# furby_shield_v1b.net
KiCad netlist of a schematic drawn in EAGLE
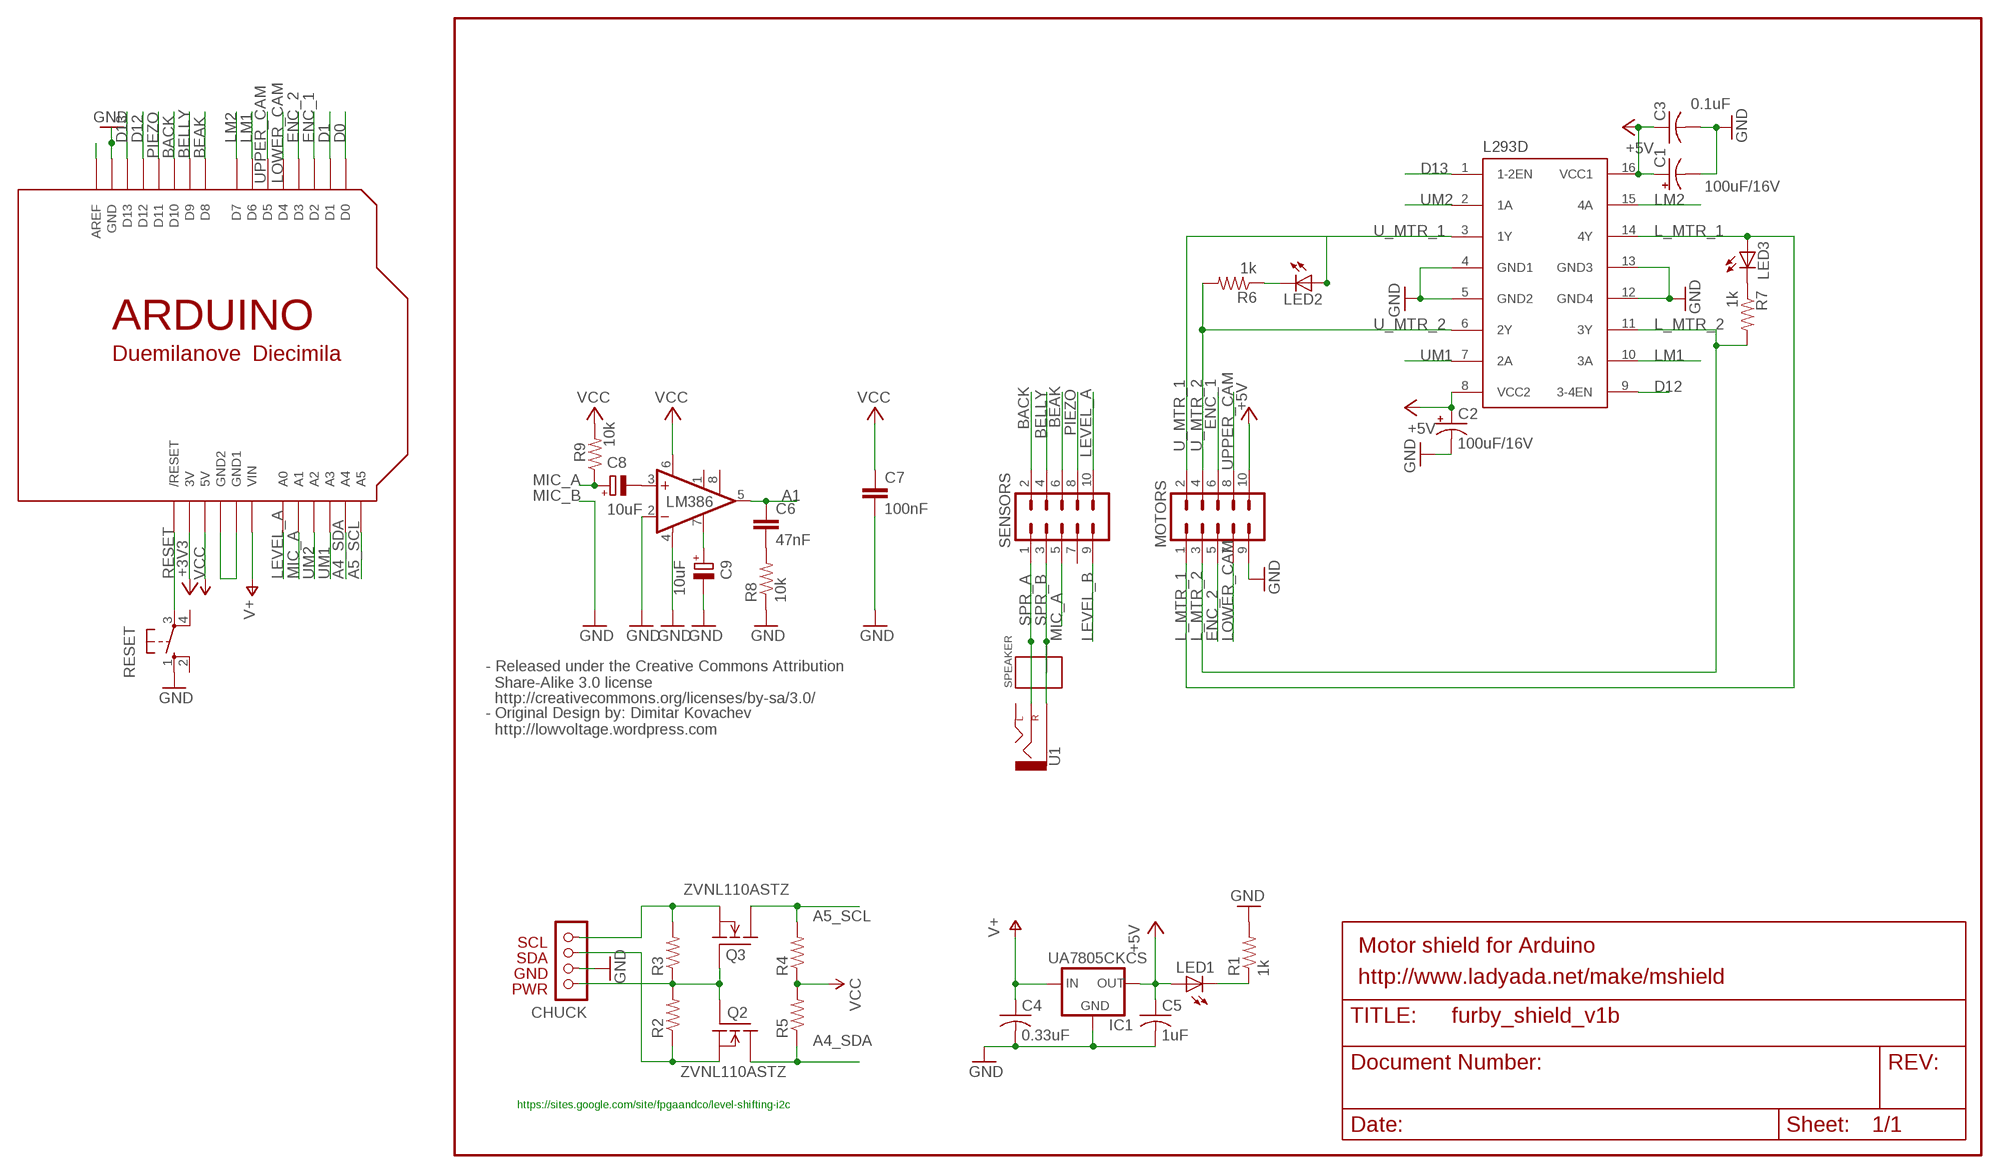
[diagram p0: schematic, sheet 1]

(export (version "E")
  (design (tool "Eeschema 10.0.6"))
  (components
    (comp (ref "C1")
      (value "100uF/16V")
      (footprint "eagle-import:E2,5-6")
      (libsource (lib "eagle-import") (part "CPOL-USE2.5-6"))
    )
    (comp (ref "C2")
      (value "100uF/16V")
      (footprint "eagle-import:E2,5-6")
      (libsource (lib "eagle-import") (part "CPOL-USE2.5-6"))
    )
    (comp (ref "C3")
      (value "0.1uF")
      (footprint "eagle-import:C025-025X050")
      (libsource (lib "eagle-import") (part "rcl-ez_C-US025-025X050"))
    )
    (comp (ref "C4")
      (value "0.33uF")
      (footprint "eagle-import:C025-024X044")
      (libsource (lib "eagle-import") (part "C-US025-024X044"))
    )
    (comp (ref "C5")
      (value "1uF")
      (footprint "eagle-import:C025-024X044")
      (libsource (lib "eagle-import") (part "C-US025-024X044"))
    )
    (comp (ref "C6")
      (value "47nF")
      (footprint "eagle-import:C025-030X050")
      (libsource (lib "eagle-import") (part "C-EU025-030X050"))
    )
    (comp (ref "C7")
      (value "100nF")
      (footprint "eagle-import:C025-025X050")
      (libsource (lib "eagle-import") (part "C-EU025-025X050"))
    )
    (comp (ref "C8")
      (value "10uF")
      (footprint "eagle-import:E2,5-6")
      (libsource (lib "eagle-import") (part "CPOL-EUE2.5-6"))
    )
    (comp (ref "C9")
      (value "10uF")
      (footprint "eagle-import:E2,5-6")
      (libsource (lib "eagle-import") (part "CPOL-EUE2.5-6"))
    )
    (comp (ref "CHUCK")
      (value "NUNCHUCK")
      (footprint "eagle-import:CONN")
      (libsource (lib "eagle-import") (part "NUNCHUCK"))
    )
    (comp (ref "IC1")
      (value "UA7805CKCS")
      (footprint "eagle-import:TO-220-ALT")
      (libsource (lib "eagle-import") (part "V_REG_78XX-TO-220"))
    )
    (comp (ref "L293D")
      (value "L293E")
      (footprint "eagle-import:DIL16")
      (libsource (lib "eagle-import") (part "L293E"))
    )
    (comp (ref "LED1")
      (value "LED3MM")
      (footprint "eagle-import:LED3MM")
      (libsource (lib "eagle-import") (part "LED3MM"))
    )
    (comp (ref "LED2")
      (value "LED3MM")
      (footprint "eagle-import:LED3MM")
      (libsource (lib "eagle-import") (part "LED3MM"))
    )
    (comp (ref "LED3")
      (value "LED3MM")
      (footprint "eagle-import:LED3MM")
      (libsource (lib "eagle-import") (part "LED3MM"))
    )
    (comp (ref "LM386")
      (value "LM386N-1")
      (footprint "eagle-import:DIL08")
      (libsource (lib "eagle-import") (part "LM386?-N1"))
    )
    (comp (ref "MOTORS")
      (value "M05X2SHD")
      (footprint "eagle-import:2X5-SHROUDED")
      (libsource (lib "eagle-import") (part "M05X2SHD"))
    )
    (comp (ref "Q2")
      (value "ZVNL110ASTZ")
      (footprint "eagle-import:TO92-INLINE")
      (libsource (lib "eagle-import") (part "FQN1N50CI"))
    )
    (comp (ref "Q3")
      (value "ZVNL110ASTZ")
      (footprint "eagle-import:TO92-INLINE")
      (libsource (lib "eagle-import") (part "FQN1N50CI"))
    )
    (comp (ref "R1")
      (value "1k")
      (footprint "eagle-import:0204_5")
      (libsource (lib "eagle-import") (part "R-US_0204/5"))
    )
    (comp (ref "R2")
      (value "R-US_0204/7")
      (footprint "eagle-import:0204_7")
      (libsource (lib "eagle-import") (part "R-US_0204/7"))
    )
    (comp (ref "R3")
      (value "R-US_0204/7")
      (footprint "eagle-import:0204_7")
      (libsource (lib "eagle-import") (part "R-US_0204/7"))
    )
    (comp (ref "R4")
      (value "R-US_0204/7")
      (footprint "eagle-import:0204_7")
      (libsource (lib "eagle-import") (part "R-US_0204/7"))
    )
    (comp (ref "R5")
      (value "R-US_0204/7")
      (footprint "eagle-import:0204_7")
      (libsource (lib "eagle-import") (part "R-US_0204/7"))
    )
    (comp (ref "R6")
      (value "1k")
      (footprint "eagle-import:0204_5")
      (libsource (lib "eagle-import") (part "R-US_0204/5"))
    )
    (comp (ref "R7")
      (value "1k")
      (footprint "eagle-import:0204_5")
      (libsource (lib "eagle-import") (part "R-US_0204/5"))
    )
    (comp (ref "R8")
      (value "10k")
      (footprint "eagle-import:0204_7")
      (libsource (lib "eagle-import") (part "R-US_0204/7"))
    )
    (comp (ref "R9")
      (value "10k")
      (footprint "eagle-import:0204_7")
      (libsource (lib "eagle-import") (part "R-US_0204/7"))
    )
    (comp (ref "RESET")
      (value "10-XX")
      (footprint "eagle-import:B3F-10XX")
      (libsource (lib "eagle-import") (part "10-XX"))
    )
    (comp (ref "SENSORS")
      (value "M05X2SHD")
      (footprint "eagle-import:2X5-SHROUDED")
      (libsource (lib "eagle-import") (part "M05X2SHD"))
    )
    (comp (ref "SPEAKER")
      (value "TERMINAL2")
      (footprint "eagle-import:TERMINAL_2")
      (libsource (lib "eagle-import") (part "TERMINAL2"))
    )
    (comp (ref "U$1")
      (value "ARDUINO-NOHOLE")
      (footprint "eagle-import:ARDUINO-NOHOLE")
      (libsource (lib "eagle-import") (part "ARDUINO-NOHOLE"))
    )
    (comp (ref "U1")
      (value "AUDIO-JACKPTH")
      (footprint "eagle-import:AUDIO-JACK")
      (libsource (lib "eagle-import") (part "AUDIO-JACKPTH"))
    )
  )
  (nets
    (net (code "1") (name "+3V3") (class "Default")
      (node (ref "CHUCK") (pin "PWR") (pinfunction "PWR_PWR") (pintype "power_in"))
      (node (ref "Q2") (pin "2") (pinfunction "G_2") (pintype "passive"))
      (node (ref "Q3") (pin "2") (pinfunction "G_2") (pintype "passive"))
      (node (ref "R2") (pin "2") (pinfunction "2_2") (pintype "passive"))
      (node (ref "R3") (pin "1") (pinfunction "1_1") (pintype "passive"))
      (node (ref "U$1") (pin "3V") (pinfunction "3V_3V") (pintype "power_in"))
    )
    (net (code "2") (name "+5V") (class "Default")
      (node (ref "C1") (pin "+") (pinfunction "+_+") (pintype "passive"))
      (node (ref "C2") (pin "+") (pinfunction "+_+") (pintype "passive"))
      (node (ref "C3") (pin "1") (pinfunction "1_1") (pintype "passive"))
      (node (ref "C5") (pin "1") (pinfunction "1_1") (pintype "passive"))
      (node (ref "IC1") (pin "OUT") (pinfunction "OUT_OUT") (pintype "output"))
      (node (ref "L293D") (pin "16") (pinfunction "VCC1_16") (pintype "power_in"))
      (node (ref "L293D") (pin "8") (pinfunction "VCC2_8") (pintype "power_in"))
      (node (ref "LED1") (pin "A") (pinfunction "A_A") (pintype "passive"))
      (node (ref "MOTORS") (pin "10") (pinfunction "10_10") (pintype "passive"))
    )
    (net (code "3") (name "/A1") (class "Default")
      (node (ref "C6") (pin "1") (pinfunction "1_1") (pintype "passive"))
      (node (ref "LM386") (pin "5") (pinfunction "OUT_5") (pintype "output"))
    )
    (net (code "4") (name "/A4_SDA") (class "Default")
      (node (ref "Q2") (pin "1") (pinfunction "D_1") (pintype "passive"))
      (node (ref "R5") (pin "1") (pinfunction "1_1") (pintype "passive"))
      (node (ref "U$1") (pin "A4") (pinfunction "A4_A4") (pintype "bidirectional"))
    )
    (net (code "5") (name "/A5_SCL") (class "Default")
      (node (ref "Q3") (pin "1") (pinfunction "D_1") (pintype "passive"))
      (node (ref "R4") (pin "2") (pinfunction "2_2") (pintype "passive"))
      (node (ref "U$1") (pin "A5") (pinfunction "A5_A5") (pintype "bidirectional"))
    )
    (net (code "6") (name "/BACK") (class "Default")
      (node (ref "SENSORS") (pin "2") (pinfunction "2_2") (pintype "passive"))
      (node (ref "U$1") (pin "D10") (pinfunction "D10_D10") (pintype "bidirectional"))
    )
    (net (code "7") (name "/BEAK") (class "Default")
      (node (ref "SENSORS") (pin "6") (pinfunction "6_6") (pintype "passive"))
      (node (ref "U$1") (pin "D8") (pinfunction "D8_D8") (pintype "bidirectional"))
    )
    (net (code "8") (name "/BELLY") (class "Default")
      (node (ref "SENSORS") (pin "4") (pinfunction "4_4") (pintype "passive"))
      (node (ref "U$1") (pin "D9") (pinfunction "D9_D9") (pintype "bidirectional"))
    )
    (net (code "9") (name "/D0") (class "Default")
      (node (ref "U$1") (pin "D0") (pinfunction "D0_D0") (pintype "bidirectional"))
    )
    (net (code "10") (name "/D1") (class "Default")
      (node (ref "U$1") (pin "D1") (pinfunction "D1_D1") (pintype "bidirectional"))
    )
    (net (code "11") (name "/D12") (class "Default")
      (node (ref "L293D") (pin "9") (pinfunction "3-4EN_9") (pintype "input"))
      (node (ref "U$1") (pin "D12") (pinfunction "D12_D12") (pintype "bidirectional"))
    )
    (net (code "12") (name "/D13") (class "Default")
      (node (ref "L293D") (pin "1") (pinfunction "1-2EN_1") (pintype "input"))
      (node (ref "U$1") (pin "D13") (pinfunction "D13_D13") (pintype "bidirectional"))
    )
    (net (code "13") (name "/ENC_1") (class "Default")
      (node (ref "MOTORS") (pin "6") (pinfunction "6_6") (pintype "passive"))
      (node (ref "U$1") (pin "D2") (pinfunction "D2_D2") (pintype "bidirectional"))
    )
    (net (code "14") (name "/ENC_2") (class "Default")
      (node (ref "MOTORS") (pin "5") (pinfunction "5_5") (pintype "passive"))
      (node (ref "U$1") (pin "D3") (pinfunction "D3_D3") (pintype "bidirectional"))
    )
    (net (code "15") (name "/LEVEL_A") (class "Default")
      (node (ref "SENSORS") (pin "10") (pinfunction "10_10") (pintype "passive"))
      (node (ref "U$1") (pin "A0") (pinfunction "A0_A0") (pintype "bidirectional"))
    )
    (net (code "16") (name "/LEVEL_B") (class "Default")
      (node (ref "SENSORS") (pin "9") (pinfunction "9_9") (pintype "passive"))
    )
    (net (code "17") (name "/LM1") (class "Default")
      (node (ref "L293D") (pin "10") (pinfunction "3A_10") (pintype "input"))
      (node (ref "U$1") (pin "D6") (pinfunction "D6_D6") (pintype "bidirectional"))
    )
    (net (code "18") (name "/LM2") (class "Default")
      (node (ref "L293D") (pin "15") (pinfunction "4A_15") (pintype "input"))
      (node (ref "U$1") (pin "D7") (pinfunction "D7_D7") (pintype "bidirectional"))
    )
    (net (code "19") (name "/LOWER_CAM") (class "Default")
      (node (ref "MOTORS") (pin "7") (pinfunction "7_7") (pintype "passive"))
      (node (ref "U$1") (pin "D4") (pinfunction "D4_D4") (pintype "bidirectional"))
    )
    (net (code "20") (name "/L_MTR_1") (class "Default")
      (node (ref "L293D") (pin "14") (pinfunction "4Y_14") (pintype "output"))
      (node (ref "LED3") (pin "A") (pinfunction "A_A") (pintype "passive"))
      (node (ref "MOTORS") (pin "1") (pinfunction "1_1") (pintype "passive"))
    )
    (net (code "21") (name "/L_MTR_2") (class "Default")
      (node (ref "L293D") (pin "11") (pinfunction "3Y_11") (pintype "output"))
      (node (ref "MOTORS") (pin "3") (pinfunction "3_3") (pintype "passive"))
      (node (ref "R7") (pin "2") (pinfunction "2_2") (pintype "passive"))
    )
    (net (code "22") (name "/MIC_A") (class "Default")
      (node (ref "C8") (pin "+") (pinfunction "+_+") (pintype "passive"))
      (node (ref "R9") (pin "1") (pinfunction "1_1") (pintype "passive"))
      (node (ref "SENSORS") (pin "5") (pinfunction "5_5") (pintype "passive"))
      (node (ref "U$1") (pin "A1") (pinfunction "A1_A1") (pintype "bidirectional"))
    )
    (net (code "23") (name "/PIEZO") (class "Default")
      (node (ref "SENSORS") (pin "8") (pinfunction "8_8") (pintype "passive"))
      (node (ref "U$1") (pin "D11") (pinfunction "D11_D11") (pintype "bidirectional"))
    )
    (net (code "24") (name "/RESET") (class "Default")
      (node (ref "RESET") (pin "3") (pinfunction "P_3") (pintype "passive"))
      (node (ref "U$1") (pin "RESET") (pinfunction "/RESET_RESET") (pintype "bidirectional"))
    )
    (net (code "25") (name "/SPR_A") (class "Default")
      (node (ref "SENSORS") (pin "1") (pinfunction "1_1") (pintype "passive"))
      (node (ref "SPEAKER") (pin "P$1") (pinfunction "P$1_P$1") (pintype "bidirectional"))
      (node (ref "U1") (pin "RING") (pinfunction "RIGHT_RING") (pintype "bidirectional"))
    )
    (net (code "26") (name "/SPR_B") (class "Default")
      (node (ref "SENSORS") (pin "3") (pinfunction "3_3") (pintype "passive"))
      (node (ref "SPEAKER") (pin "P$2") (pinfunction "P$2_P$2") (pintype "bidirectional"))
      (node (ref "U1") (pin "SLEEVE") (pinfunction "SLEEVE_SLEEVE") (pintype "bidirectional"))
    )
    (net (code "27") (name "/UM1") (class "Default")
      (node (ref "L293D") (pin "7") (pinfunction "2A_7") (pintype "input"))
      (node (ref "U$1") (pin "A3") (pinfunction "A3_A3") (pintype "bidirectional"))
    )
    (net (code "28") (name "/UM2") (class "Default")
      (node (ref "L293D") (pin "2") (pinfunction "1A_2") (pintype "input"))
      (node (ref "U$1") (pin "A2") (pinfunction "A2_A2") (pintype "bidirectional"))
    )
    (net (code "29") (name "/UPPER_CAM") (class "Default")
      (node (ref "MOTORS") (pin "8") (pinfunction "8_8") (pintype "passive"))
      (node (ref "U$1") (pin "D5") (pinfunction "D5_D5") (pintype "bidirectional"))
    )
    (net (code "30") (name "/U_MTR_1") (class "Default")
      (node (ref "L293D") (pin "3") (pinfunction "1Y_3") (pintype "output"))
      (node (ref "LED2") (pin "A") (pinfunction "A_A") (pintype "passive"))
      (node (ref "MOTORS") (pin "2") (pinfunction "2_2") (pintype "passive"))
    )
    (net (code "31") (name "/U_MTR_2") (class "Default")
      (node (ref "L293D") (pin "6") (pinfunction "2Y_6") (pintype "output"))
      (node (ref "MOTORS") (pin "4") (pinfunction "4_4") (pintype "passive"))
      (node (ref "R6") (pin "2") (pinfunction "2_2") (pintype "passive"))
    )
    (net (code "32") (name "GND") (class "Default")
      (node (ref "C1") (pin "-") (pinfunction "-_-") (pintype "passive"))
      (node (ref "C2") (pin "-") (pinfunction "-_-") (pintype "passive"))
      (node (ref "C3") (pin "2") (pinfunction "2_2") (pintype "passive"))
      (node (ref "C4") (pin "2") (pinfunction "2_2") (pintype "passive"))
      (node (ref "C5") (pin "2") (pinfunction "2_2") (pintype "passive"))
      (node (ref "C7") (pin "2") (pinfunction "2_2") (pintype "passive"))
      (node (ref "C9") (pin "-") (pinfunction "-_-") (pintype "passive"))
      (node (ref "CHUCK") (pin "GND") (pinfunction "GND_GND") (pintype "passive"))
      (node (ref "IC1") (pin "GND") (pinfunction "GND_GND") (pintype "input"))
      (node (ref "L293D") (pin "12") (pinfunction "GND4_12") (pintype "power_in"))
      (node (ref "L293D") (pin "13") (pinfunction "GND3_13") (pintype "power_in"))
      (node (ref "L293D") (pin "4") (pinfunction "GND1_4") (pintype "power_in"))
      (node (ref "L293D") (pin "5") (pinfunction "GND2_5") (pintype "power_in"))
      (node (ref "LM386") (pin "2") (pinfunction "-IN_2") (pintype "input"))
      (node (ref "LM386") (pin "4") (pinfunction "GND_4") (pintype "power_in"))
      (node (ref "MOTORS") (pin "9") (pinfunction "9_9") (pintype "passive"))
      (node (ref "R1") (pin "2") (pinfunction "2_2") (pintype "passive"))
      (node (ref "R8") (pin "1") (pinfunction "1_1") (pintype "passive"))
      (node (ref "RESET") (pin "1") (pinfunction "S_1") (pintype "passive"))
      (node (ref "U$1") (pin "GND") (pinfunction "GND_GND") (pintype "power_in"))
      (node (ref "U$1") (pin "GND1") (pinfunction "GND1_GND1") (pintype "power_in"))
      (node (ref "U$1") (pin "GND2") (pinfunction "GND2_GND2") (pintype "power_in"))
    )
    (net (code "33") (name "Net-(C6-Pad2)") (class "Default")
      (node (ref "C6") (pin "2") (pinfunction "2_2") (pintype "passive"))
      (node (ref "R8") (pin "2") (pinfunction "2_2") (pintype "passive"))
    )
    (net (code "34") (name "Net-(LED1-C)") (class "Default")
      (node (ref "LED1") (pin "K") (pinfunction "C_K") (pintype "passive"))
      (node (ref "R1") (pin "1") (pinfunction "1_1") (pintype "passive"))
    )
    (net (code "35") (name "Net-(LED2-C)") (class "Default")
      (node (ref "LED2") (pin "K") (pinfunction "C_K") (pintype "passive"))
      (node (ref "R6") (pin "1") (pinfunction "1_1") (pintype "passive"))
    )
    (net (code "36") (name "Net-(LED3-C)") (class "Default")
      (node (ref "LED3") (pin "K") (pinfunction "C_K") (pintype "passive"))
      (node (ref "R7") (pin "1") (pinfunction "1_1") (pintype "passive"))
    )
    (net (code "37") (name "Net-(LM386-+IN)") (class "Default")
      (node (ref "C8") (pin "-") (pinfunction "-_-") (pintype "passive"))
      (node (ref "LM386") (pin "3") (pinfunction "+IN_3") (pintype "input"))
    )
    (net (code "38") (name "Net-(LM386-BYPASS)") (class "Default")
      (node (ref "C9") (pin "+") (pinfunction "+_+") (pintype "passive"))
      (node (ref "LM386") (pin "7") (pinfunction "BYPASS_7") (pintype "passive"))
    )
    (net (code "39") (name "Net-(Q2-S)") (class "Default")
      (node (ref "CHUCK") (pin "SDA") (pinfunction "SDA_SDA") (pintype "bidirectional"))
      (node (ref "Q2") (pin "3") (pinfunction "S_3") (pintype "passive"))
      (node (ref "R2") (pin "1") (pinfunction "1_1") (pintype "passive"))
    )
    (net (code "40") (name "Net-(Q3-S)") (class "Default")
      (node (ref "CHUCK") (pin "SCL") (pinfunction "SCL_SCL") (pintype "bidirectional"))
      (node (ref "Q3") (pin "3") (pinfunction "S_3") (pintype "passive"))
      (node (ref "R3") (pin "2") (pinfunction "2_2") (pintype "passive"))
    )
    (net (code "41") (name "V+") (class "Default")
      (node (ref "C4") (pin "1") (pinfunction "1_1") (pintype "passive"))
      (node (ref "IC1") (pin "IN") (pinfunction "IN_IN") (pintype "input"))
      (node (ref "U$1") (pin "VIN") (pinfunction "VIN_VIN") (pintype "power_in"))
    )
    (net (code "42") (name "VCC") (class "Default")
      (node (ref "C7") (pin "1") (pinfunction "1_1") (pintype "passive"))
      (node (ref "LM386") (pin "6") (pinfunction "VS_6") (pintype "power_in"))
      (node (ref "R4") (pin "1") (pinfunction "1_1") (pintype "passive"))
      (node (ref "R5") (pin "2") (pinfunction "2_2") (pintype "passive"))
      (node (ref "R9") (pin "2") (pinfunction "2_2") (pintype "passive"))
      (node (ref "U$1") (pin "5V") (pinfunction "5V_5V") (pintype "power_in"))
      (node (ref "U$1") (pin "AREF") (pinfunction "AREF_AREF") (pintype "bidirectional"))
    )
    (net (code "43") (name "unconnected-(LM386-GAIN-Pad1)") (class "Default")
      (node (ref "LM386") (pin "1") (pinfunction "GAIN_1") (pintype "passive"))
    )
    (net (code "44") (name "unconnected-(LM386-GAIN-Pad8)") (class "Default")
      (node (ref "LM386") (pin "8") (pinfunction "GAIN_8") (pintype "passive"))
    )
    (net (code "45") (name "unconnected-(RESET-P1-Pad4)") (class "Default")
      (node (ref "RESET") (pin "4") (pinfunction "P1_4") (pintype "passive"))
    )
    (net (code "46") (name "unconnected-(RESET-S1-Pad2)") (class "Default")
      (node (ref "RESET") (pin "2") (pinfunction "S1_2") (pintype "passive"))
    )
    (net (code "47") (name "unconnected-(SENSORS-Pad7)") (class "Default")
      (node (ref "SENSORS") (pin "7") (pinfunction "7_7") (pintype "passive"))
    )
    (net (code "48") (name "unconnected-(U1-LEFT-PadTIP)") (class "Default")
      (node (ref "U1") (pin "TIP") (pinfunction "LEFT_TIP") (pintype "bidirectional"))
    )
  )
)
